# MCU.net
KiCad netlist of a schematic drawn in Altium Designer
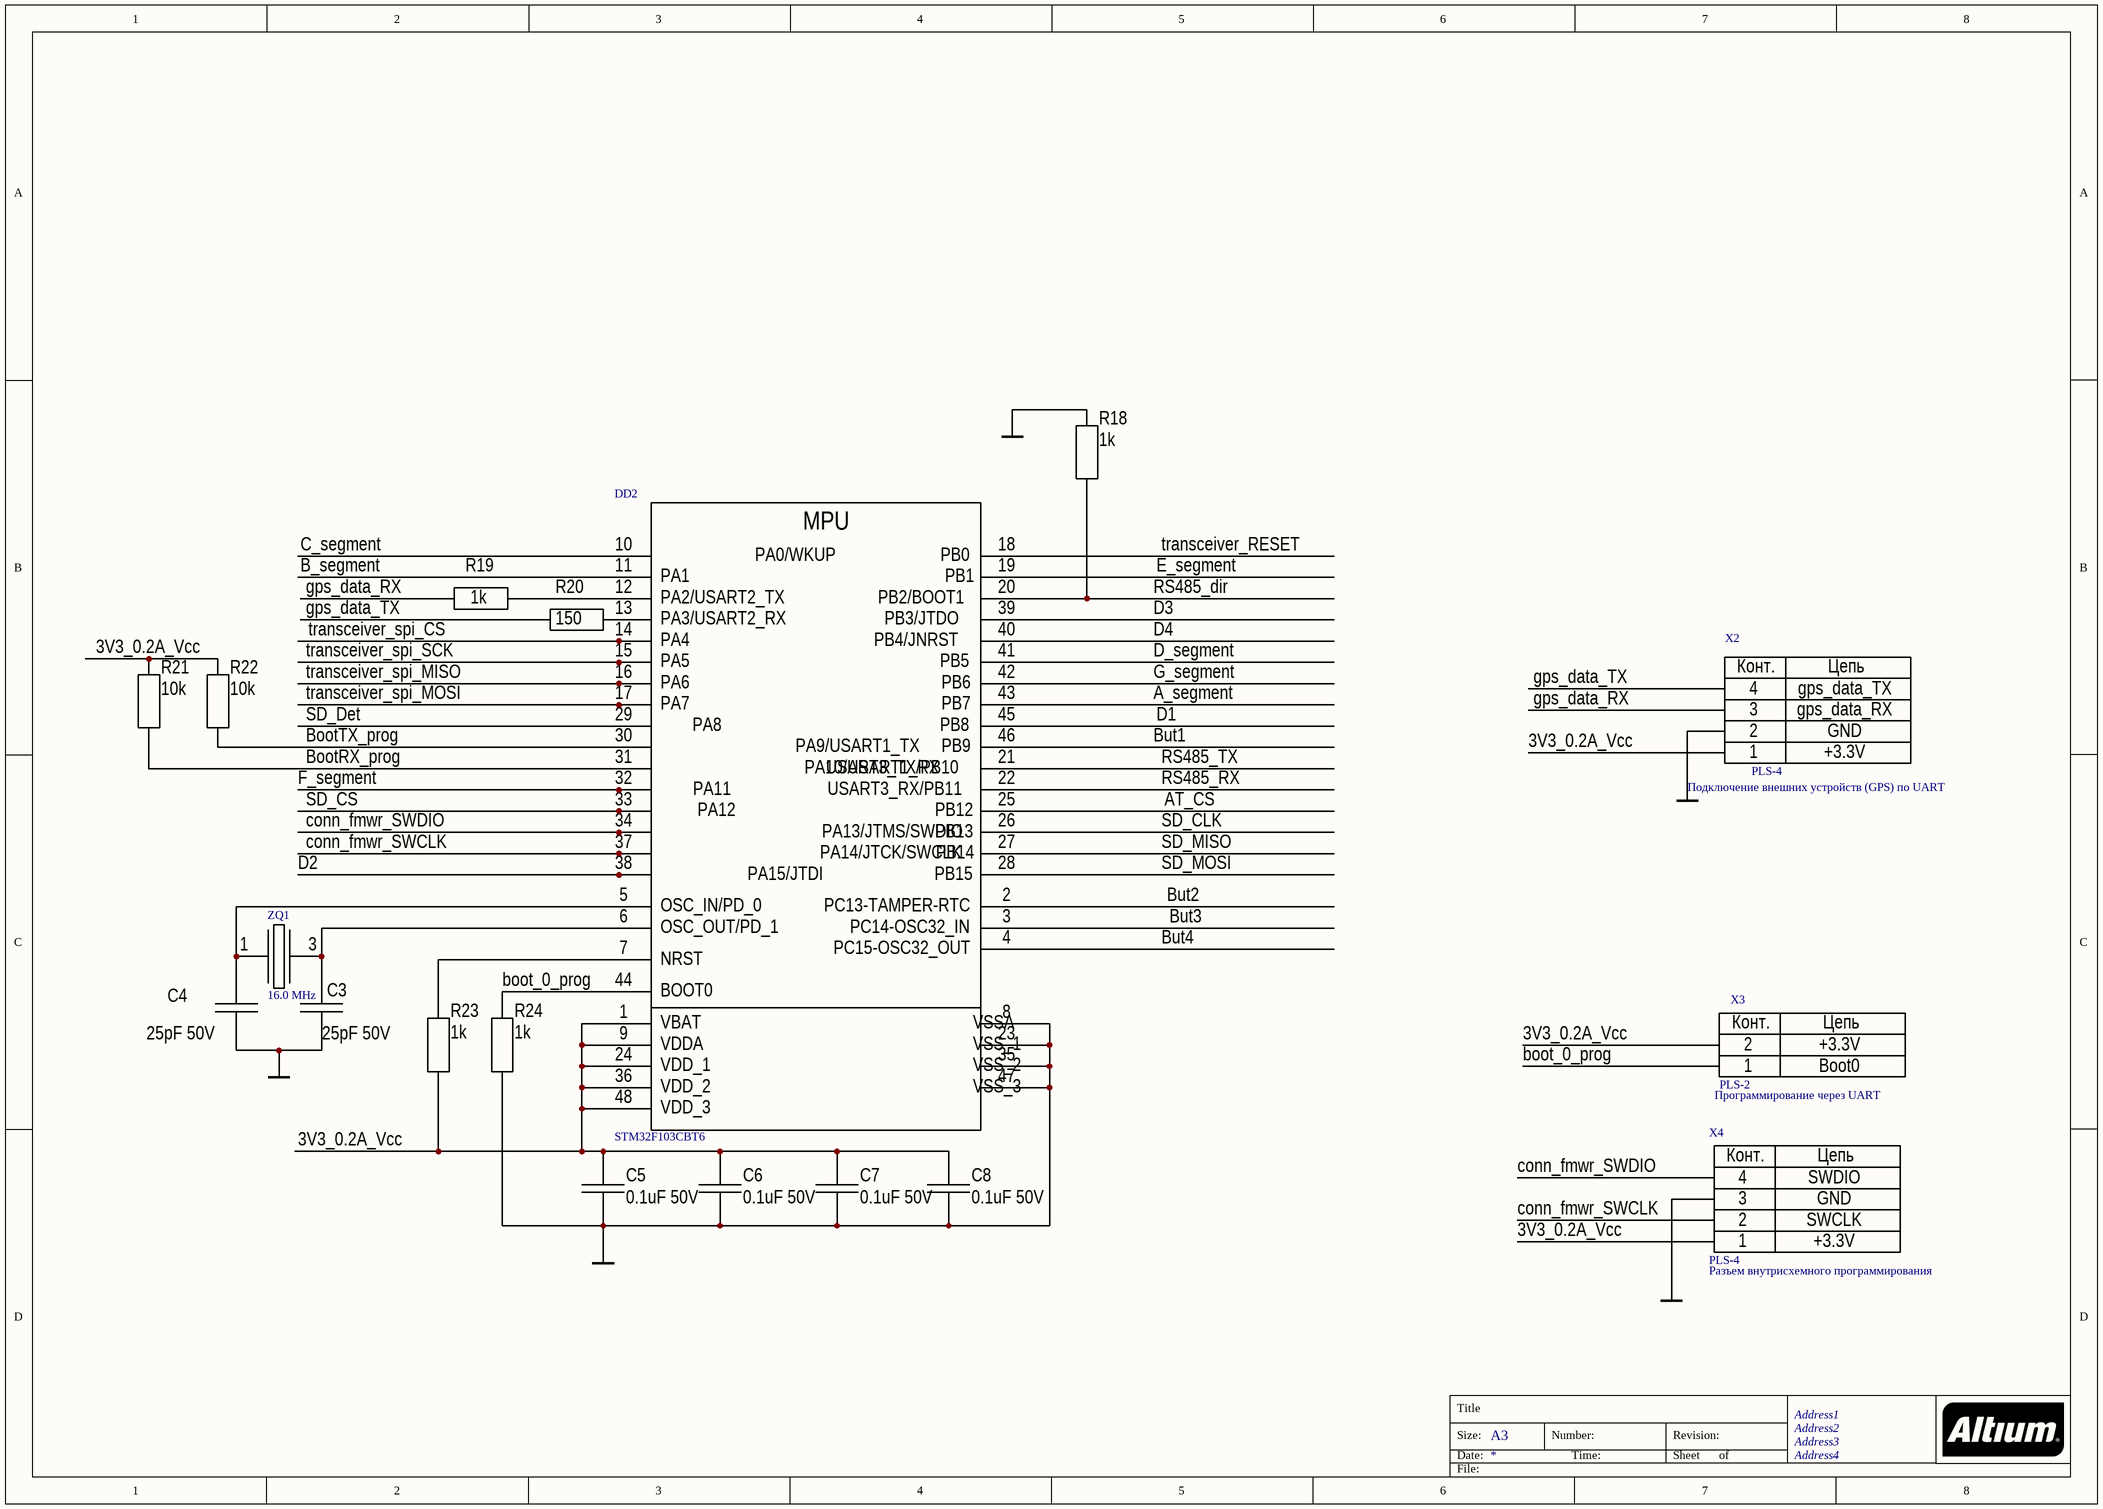
[diagram p0: MCU.SchDoc]

(export (version "E")
  (design (tool "Eeschema 10.0.6"))
  (components
    (comp (ref "C3")
      (value "25pF 50V")
      (footprint "0805_CAP")
      (libsource (lib "Integrated_Library_tikhovikt") (part "Cap_np"))
    )
    (comp (ref "C4")
      (value "25pF 50V")
      (footprint "0805_CAP")
      (libsource (lib "Integrated_Library_tikhovikt") (part "Cap_np"))
    )
    (comp (ref "C5")
      (value "0.1uF 50V")
      (footprint "0805_CAP")
      (libsource (lib "Integrated_Library_tikhovikt") (part "Cap_np"))
    )
    (comp (ref "C6")
      (value "0.1uF 50V")
      (footprint "0805_CAP")
      (libsource (lib "Integrated_Library_tikhovikt") (part "Cap_np"))
    )
    (comp (ref "C7")
      (value "0.1uF 50V")
      (footprint "0805_CAP")
      (libsource (lib "Integrated_Library_tikhovikt") (part "Cap_np"))
    )
    (comp (ref "C8")
      (value "0.1uF 50V")
      (footprint "0805_CAP")
      (libsource (lib "Integrated_Library_tikhovikt") (part "Cap_np"))
    )
    (comp (ref "DD2")
      (value "STM32F103CBT6")
      (footprint "Lqfp-48")
      (libsource (lib "Integrated_Library_tikhovikt") (part "STM32F103-48"))
    )
    (comp (ref "R18")
      (value "1k")
      (footprint "0805_RES")
      (libsource (lib "Integrated_Library_tikhovikt") (part "Res"))
    )
    (comp (ref "R19")
      (value "1k")
      (footprint "0805_RES")
      (libsource (lib "Integrated_Library_tikhovikt") (part "Res"))
    )
    (comp (ref "R20")
      (value "150")
      (footprint "0805_RES")
      (libsource (lib "Integrated_Library_tikhovikt") (part "Res"))
    )
    (comp (ref "R21")
      (value "10k")
      (footprint "0805_RES")
      (libsource (lib "Integrated_Library_tikhovikt") (part "Res"))
    )
    (comp (ref "R22")
      (value "10k")
      (footprint "0805_RES")
      (libsource (lib "Integrated_Library_tikhovikt") (part "Res"))
    )
    (comp (ref "R23")
      (value "1k")
      (footprint "0805_RES")
      (libsource (lib "Integrated_Library_tikhovikt") (part "Res"))
    )
    (comp (ref "R24")
      (value "1k")
      (footprint "0805_RES")
      (libsource (lib "Integrated_Library_tikhovikt") (part "Res"))
    )
    (comp (ref "X2")
      (value "PLS-4")
      (footprint "PLS-4-2.54")
      (fields (field (name "DESTINY") "Подключение внешних устройств (GPS) по UART"))
      (libsource (lib "") (part "4pin_conn_1"))
    )
    (comp (ref "X3")
      (value "PLS-2")
      (footprint "PLS-2-2.54")
      (fields (field (name "DESTINY") "Программирование через UART"))
      (libsource (lib "Integrated_Library_tikhovikt") (part "2pin_conn"))
    )
    (comp (ref "X4")
      (value "PLS-4")
      (footprint "PLS-4-2.54")
      (fields (field (name "DESTINY") "Разъем внутрисхемного программирования"))
      (libsource (lib "Integrated_Library_tikhovikt") (part "4pin_conn"))
    )
    (comp (ref "ZQ1")
      (value "16.0 MHz")
      (footprint "HC-49")
      (libsource (lib "Integrated_Library_tikhovikt") (part "Cristall"))
    )
  )
  (nets
    (net (code "1") (name "/3V3_0.2A_Vcc") (class "Default")
      (node (ref "C5") (pin "2") (pinfunction "2_2") (pintype "passive"))
      (node (ref "C6") (pin "2") (pinfunction "2_2") (pintype "passive"))
      (node (ref "C7") (pin "2") (pinfunction "2_2") (pintype "passive"))
      (node (ref "C8") (pin "2") (pinfunction "2_2") (pintype "passive"))
      (node (ref "DD2") (pin "1") (pinfunction "1_1") (pintype "passive"))
      (node (ref "DD2") (pin "24") (pinfunction "24_24") (pintype "passive"))
      (node (ref "DD2") (pin "36") (pinfunction "36_36") (pintype "passive"))
      (node (ref "DD2") (pin "48") (pinfunction "48_48") (pintype "passive"))
      (node (ref "DD2") (pin "9") (pinfunction "9_9") (pintype "passive"))
      (node (ref "R21") (pin "2") (pinfunction "2_2") (pintype "passive"))
      (node (ref "R22") (pin "2") (pinfunction "2_2") (pintype "passive"))
      (node (ref "R23") (pin "1") (pinfunction "1_1") (pintype "passive"))
      (node (ref "X2") (pin "1") (pinfunction "1_1") (pintype "passive"))
      (node (ref "X3") (pin "2") (pinfunction "2_2") (pintype "passive"))
      (node (ref "X4") (pin "1") (pinfunction "1_1") (pintype "passive"))
    )
    (net (code "2") (name "/AT_CS") (class "Default")
      (node (ref "DD2") (pin "25") (pinfunction "25_25") (pintype "passive"))
    )
    (net (code "3") (name "/A_segment") (class "Default")
      (node (ref "DD2") (pin "43") (pinfunction "43_43") (pintype "passive"))
    )
    (net (code "4") (name "/B_segment") (class "Default")
      (node (ref "DD2") (pin "11") (pinfunction "11_11") (pintype "passive"))
    )
    (net (code "5") (name "/BootRX_prog") (class "Default")
      (node (ref "DD2") (pin "31") (pinfunction "31_31") (pintype "passive"))
      (node (ref "R21") (pin "1") (pinfunction "1_1") (pintype "passive"))
    )
    (net (code "6") (name "/BootTX_prog") (class "Default")
      (node (ref "DD2") (pin "30") (pinfunction "30_30") (pintype "passive"))
      (node (ref "R22") (pin "1") (pinfunction "1_1") (pintype "passive"))
    )
    (net (code "7") (name "/But1") (class "Default")
      (node (ref "DD2") (pin "46") (pinfunction "46_46") (pintype "passive"))
    )
    (net (code "8") (name "/But2") (class "Default")
      (node (ref "DD2") (pin "2") (pinfunction "2_2") (pintype "passive"))
    )
    (net (code "9") (name "/But3") (class "Default")
      (node (ref "DD2") (pin "3") (pinfunction "3_3") (pintype "passive"))
    )
    (net (code "10") (name "/But4") (class "Default")
      (node (ref "DD2") (pin "4") (pinfunction "4_4") (pintype "passive"))
    )
    (net (code "11") (name "/C_segment") (class "Default")
      (node (ref "DD2") (pin "10") (pinfunction "10_10") (pintype "passive"))
    )
    (net (code "12") (name "/D1") (class "Default")
      (node (ref "DD2") (pin "45") (pinfunction "45_45") (pintype "passive"))
    )
    (net (code "13") (name "/D2") (class "Default")
      (node (ref "DD2") (pin "38") (pinfunction "38_38") (pintype "passive"))
    )
    (net (code "14") (name "/D3") (class "Default")
      (node (ref "DD2") (pin "39") (pinfunction "39_39") (pintype "passive"))
    )
    (net (code "15") (name "/D4") (class "Default")
      (node (ref "DD2") (pin "40") (pinfunction "40_40") (pintype "passive"))
    )
    (net (code "16") (name "/D_segment") (class "Default")
      (node (ref "DD2") (pin "41") (pinfunction "41_41") (pintype "passive"))
    )
    (net (code "17") (name "/E_segment") (class "Default")
      (node (ref "DD2") (pin "19") (pinfunction "19_19") (pintype "passive"))
    )
    (net (code "18") (name "/F_segment") (class "Default")
      (node (ref "DD2") (pin "32") (pinfunction "32_32") (pintype "passive"))
    )
    (net (code "19") (name "/G_segment") (class "Default")
      (node (ref "DD2") (pin "42") (pinfunction "42_42") (pintype "passive"))
    )
    (net (code "20") (name "/RS485_RX") (class "Default")
      (node (ref "DD2") (pin "22") (pinfunction "22_22") (pintype "passive"))
    )
    (net (code "21") (name "/RS485_TX") (class "Default")
      (node (ref "DD2") (pin "21") (pinfunction "21_21") (pintype "passive"))
    )
    (net (code "22") (name "/RS485_dir") (class "Default")
      (node (ref "DD2") (pin "20") (pinfunction "20_20") (pintype "passive"))
      (node (ref "R18") (pin "1") (pinfunction "1_1") (pintype "passive"))
    )
    (net (code "23") (name "/SD_CLK") (class "Default")
      (node (ref "DD2") (pin "26") (pinfunction "26_26") (pintype "passive"))
    )
    (net (code "24") (name "/SD_CS") (class "Default")
      (node (ref "DD2") (pin "33") (pinfunction "33_33") (pintype "passive"))
    )
    (net (code "25") (name "/SD_Det") (class "Default")
      (node (ref "DD2") (pin "29") (pinfunction "29_29") (pintype "passive"))
    )
    (net (code "26") (name "/SD_MISO") (class "Default")
      (node (ref "DD2") (pin "27") (pinfunction "27_27") (pintype "passive"))
    )
    (net (code "27") (name "/SD_MOSI") (class "Default")
      (node (ref "DD2") (pin "28") (pinfunction "28_28") (pintype "passive"))
    )
    (net (code "28") (name "/boot_0_prog") (class "Default")
      (node (ref "DD2") (pin "44") (pinfunction "44_44") (pintype "passive"))
      (node (ref "R24") (pin "2") (pinfunction "2_2") (pintype "passive"))
      (node (ref "X3") (pin "1") (pinfunction "1_1") (pintype "passive"))
    )
    (net (code "29") (name "/conn_fmwr_SWCLK") (class "Default")
      (node (ref "DD2") (pin "37") (pinfunction "37_37") (pintype "passive"))
      (node (ref "X4") (pin "2") (pinfunction "2_2") (pintype "passive"))
    )
    (net (code "30") (name "/conn_fmwr_SWDIO") (class "Default")
      (node (ref "DD2") (pin "34") (pinfunction "34_34") (pintype "passive"))
      (node (ref "X4") (pin "4") (pinfunction "4_4") (pintype "passive"))
    )
    (net (code "31") (name "/gps_data_RX") (class "Default")
      (node (ref "R19") (pin "2") (pinfunction "2_2") (pintype "passive"))
      (node (ref "X2") (pin "3") (pinfunction "3_3") (pintype "passive"))
    )
    (net (code "32") (name "/gps_data_TX") (class "Default")
      (node (ref "R20") (pin "2") (pinfunction "2_2") (pintype "passive"))
      (node (ref "X2") (pin "4") (pinfunction "4_4") (pintype "passive"))
    )
    (net (code "33") (name "/transceiver_RESET") (class "Default")
      (node (ref "DD2") (pin "18") (pinfunction "18_18") (pintype "passive"))
    )
    (net (code "34") (name "/transceiver_spi_CS") (class "Default")
      (node (ref "DD2") (pin "14") (pinfunction "14_14") (pintype "passive"))
    )
    (net (code "35") (name "/transceiver_spi_MISO") (class "Default")
      (node (ref "DD2") (pin "16") (pinfunction "16_16") (pintype "passive"))
    )
    (net (code "36") (name "/transceiver_spi_MOSI") (class "Default")
      (node (ref "DD2") (pin "17") (pinfunction "17_17") (pintype "passive"))
    )
    (net (code "37") (name "/transceiver_spi_SCK") (class "Default")
      (node (ref "DD2") (pin "15") (pinfunction "15_15") (pintype "passive"))
    )
    (net (code "38") (name "GND") (class "Default")
      (node (ref "C3") (pin "1") (pinfunction "1_1") (pintype "passive"))
      (node (ref "C4") (pin "1") (pinfunction "1_1") (pintype "passive"))
      (node (ref "C5") (pin "1") (pinfunction "1_1") (pintype "passive"))
      (node (ref "C6") (pin "1") (pinfunction "1_1") (pintype "passive"))
      (node (ref "C7") (pin "1") (pinfunction "1_1") (pintype "passive"))
      (node (ref "C8") (pin "1") (pinfunction "1_1") (pintype "passive"))
      (node (ref "DD2") (pin "23") (pinfunction "23_23") (pintype "passive"))
      (node (ref "DD2") (pin "35") (pinfunction "35_35") (pintype "passive"))
      (node (ref "DD2") (pin "47") (pinfunction "47_47") (pintype "passive"))
      (node (ref "DD2") (pin "8") (pinfunction "8_8") (pintype "passive"))
      (node (ref "R18") (pin "2") (pinfunction "2_2") (pintype "passive"))
      (node (ref "R24") (pin "1") (pinfunction "1_1") (pintype "passive"))
      (node (ref "X2") (pin "2") (pinfunction "2_2") (pintype "passive"))
      (node (ref "X4") (pin "3") (pinfunction "3_3") (pintype "passive"))
    )
    (net (code "39") (name "Net-(C3-Pad2)") (class "Default")
      (node (ref "C3") (pin "2") (pinfunction "2_2") (pintype "passive"))
      (node (ref "DD2") (pin "6") (pinfunction "6_6") (pintype "passive"))
      (node (ref "ZQ1") (pin "3") (pinfunction "3_3") (pintype "passive"))
    )
    (net (code "40") (name "Net-(C4-Pad2)") (class "Default")
      (node (ref "C4") (pin "2") (pinfunction "2_2") (pintype "passive"))
      (node (ref "DD2") (pin "5") (pinfunction "5_5") (pintype "passive"))
      (node (ref "ZQ1") (pin "1") (pinfunction "1_1") (pintype "passive"))
    )
    (net (code "41") (name "Net-(DD2-Pad7)") (class "Default")
      (node (ref "DD2") (pin "7") (pinfunction "7_7") (pintype "passive"))
      (node (ref "R23") (pin "2") (pinfunction "2_2") (pintype "passive"))
    )
    (net (code "42") (name "Net-(DD2-Pad12)") (class "Default")
      (node (ref "DD2") (pin "12") (pinfunction "12_12") (pintype "passive"))
      (node (ref "R19") (pin "1") (pinfunction "1_1") (pintype "passive"))
    )
    (net (code "43") (name "Net-(DD2-Pad13)") (class "Default")
      (node (ref "DD2") (pin "13") (pinfunction "13_13") (pintype "passive"))
      (node (ref "R20") (pin "1") (pinfunction "1_1") (pintype "passive"))
    )
  )
)
